# LCD_Disp_AIR.net
KiCad netlist of a schematic drawn in EAGLE
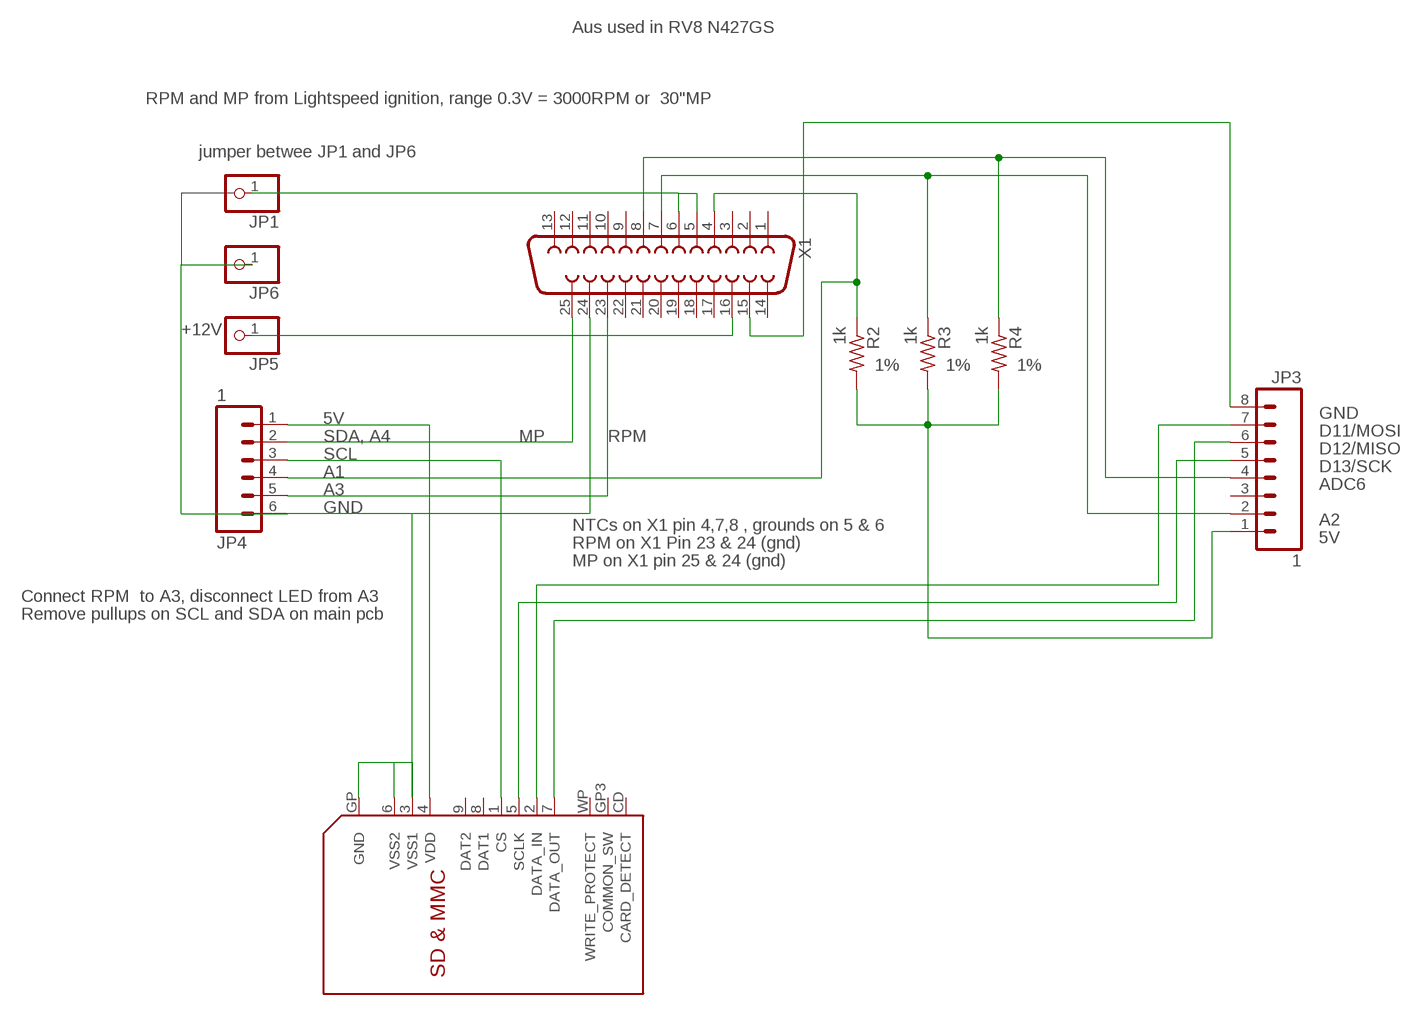
[diagram p0: schematic, sheet 1]

(export (version "E")
  (design (tool "Eeschema 10.0.6"))
  (components
    (comp (ref "JP1")
      (value "PINHD-1X1CB")
      (footprint "eagle-import:1X01-CLEANBIG")
      (libsource (lib "eagle-import") (part "PINHD-1X1CB"))
    )
    (comp (ref "JP3")
      (value "1")
      (footprint "eagle-import:1X08")
      (libsource (lib "eagle-import") (part "M081X08"))
    )
    (comp (ref "JP4")
      (value "1")
      (footprint "eagle-import:1X06")
      (libsource (lib "eagle-import") (part "M06SIP"))
    )
    (comp (ref "JP5")
      (value "PINHD-1X1")
      (footprint "eagle-import:1X01")
      (libsource (lib "eagle-import") (part "PINHD-1X1"))
    )
    (comp (ref "JP6")
      (value "PINHD-1X1CB")
      (footprint "eagle-import:1X01-CLEANBIG")
      (libsource (lib "eagle-import") (part "PINHD-1X1CB"))
    )
    (comp (ref "R2")
      (value "1k")
      (footprint "eagle-import:0204_7")
      (libsource (lib "eagle-import") (part "R-US_0204/7"))
    )
    (comp (ref "R3")
      (value "1k")
      (footprint "eagle-import:0204_7")
      (libsource (lib "eagle-import") (part "R-US_0204/7"))
    )
    (comp (ref "R4")
      (value "1k")
      (footprint "eagle-import:0204_7")
      (libsource (lib "eagle-import") (part "R-US_0204/7"))
    )
    (comp (ref "U$1")
      (value "SDMMC06132")
      (footprint "eagle-import:06132")
      (libsource (lib "eagle-import") (part "SDMMC06132"))
    )
    (comp (ref "X1")
      (value "DB25_FEMALEVB")
      (footprint "eagle-import:F25VB")
      (libsource (lib "eagle-import") (part "DB25_FEMALEVB"))
    )
  )
  (nets
    (net (code "1") (name "/+12V") (class "Default")
      (node (ref "JP5") (pin "1") (pinfunction "1_1") (pintype "passive"))
      (node (ref "X1") (pin "16") (pinfunction "16_16") (pintype "passive"))
    )
    (net (code "2") (name "Net-(JP1-Pad1)") (class "Default")
      (node (ref "JP1") (pin "1") (pinfunction "1_1") (pintype "passive"))
      (node (ref "X1") (pin "5") (pinfunction "5_5") (pintype "passive"))
      (node (ref "X1") (pin "6") (pinfunction "6_6") (pintype "passive"))
    )
    (net (code "3") (name "Net-(JP3-Pad1)") (class "Default")
      (node (ref "JP3") (pin "1") (pinfunction "1_1") (pintype "passive"))
      (node (ref "R2") (pin "2") (pinfunction "2_2") (pintype "passive"))
      (node (ref "R3") (pin "2") (pinfunction "2_2") (pintype "passive"))
      (node (ref "R4") (pin "2") (pinfunction "2_2") (pintype "passive"))
    )
    (net (code "4") (name "Net-(JP3-Pad2)") (class "Default")
      (node (ref "JP3") (pin "2") (pinfunction "2_2") (pintype "passive"))
      (node (ref "R3") (pin "1") (pinfunction "1_1") (pintype "passive"))
      (node (ref "X1") (pin "7") (pinfunction "7_7") (pintype "passive"))
    )
    (net (code "5") (name "Net-(JP3-Pad4)") (class "Default")
      (node (ref "JP3") (pin "4") (pinfunction "4_4") (pintype "passive"))
      (node (ref "R4") (pin "1") (pinfunction "1_1") (pintype "passive"))
      (node (ref "X1") (pin "8") (pinfunction "8_8") (pintype "passive"))
    )
    (net (code "6") (name "Net-(JP3-Pad8)") (class "Default")
      (node (ref "JP3") (pin "8") (pinfunction "8_8") (pintype "passive"))
      (node (ref "X1") (pin "15") (pinfunction "15_15") (pintype "passive"))
    )
    (net (code "7") (name "Net-(JP4-Pad2)") (class "Default")
      (node (ref "JP4") (pin "2") (pinfunction "2_2") (pintype "passive"))
      (node (ref "X1") (pin "25") (pinfunction "25_25") (pintype "passive"))
    )
    (net (code "8") (name "Net-(JP4-Pad4)") (class "Default")
      (node (ref "JP4") (pin "4") (pinfunction "4_4") (pintype "passive"))
      (node (ref "R2") (pin "1") (pinfunction "1_1") (pintype "passive"))
      (node (ref "X1") (pin "4") (pinfunction "4_4") (pintype "passive"))
    )
    (net (code "9") (name "Net-(JP4-Pad5)") (class "Default")
      (node (ref "JP4") (pin "5") (pinfunction "5_5") (pintype "passive"))
      (node (ref "X1") (pin "23") (pinfunction "23_23") (pintype "passive"))
    )
    (net (code "10") (name "Net-(U$1-CS)") (class "Default")
      (node (ref "JP4") (pin "3") (pinfunction "3_3") (pintype "passive"))
      (node (ref "U$1") (pin "1") (pinfunction "CS_1") (pintype "input"))
    )
    (net (code "11") (name "Net-(U$1-DATA_IN)") (class "Default")
      (node (ref "JP3") (pin "7") (pinfunction "7_7") (pintype "passive"))
      (node (ref "U$1") (pin "2") (pinfunction "DATA_IN_2") (pintype "input"))
    )
    (net (code "12") (name "Net-(U$1-DATA_OUT)") (class "Default")
      (node (ref "JP3") (pin "6") (pinfunction "6_6") (pintype "passive"))
      (node (ref "U$1") (pin "7") (pinfunction "DATA_OUT_7") (pintype "output"))
    )
    (net (code "13") (name "Net-(U$1-GND)") (class "Default")
      (node (ref "JP4") (pin "6") (pinfunction "6_6") (pintype "passive"))
      (node (ref "JP6") (pin "1") (pinfunction "1_1") (pintype "passive"))
      (node (ref "U$1") (pin "3") (pinfunction "VSS1_3") (pintype "power_in"))
      (node (ref "U$1") (pin "6") (pinfunction "VSS2_6") (pintype "power_in"))
      (node (ref "U$1") (pin "GP") (pinfunction "GND_GP") (pintype "power_in"))
      (node (ref "X1") (pin "24") (pinfunction "24_24") (pintype "passive"))
    )
    (net (code "14") (name "Net-(U$1-SCLK)") (class "Default")
      (node (ref "JP3") (pin "5") (pinfunction "5_5") (pintype "passive"))
      (node (ref "U$1") (pin "5") (pinfunction "SCLK_5") (pintype "input"))
    )
    (net (code "15") (name "Net-(U$1-VDD)") (class "Default")
      (node (ref "JP4") (pin "1") (pinfunction "1_1") (pintype "passive"))
      (node (ref "U$1") (pin "4") (pinfunction "VDD_4") (pintype "power_in"))
    )
    (net (code "16") (name "unconnected-(JP3-Pad3)") (class "Default")
      (node (ref "JP3") (pin "3") (pinfunction "3_3") (pintype "passive"))
    )
    (net (code "17") (name "unconnected-(U$1-CARD_DETECT-PadCD)") (class "Default")
      (node (ref "U$1") (pin "CD") (pinfunction "CARD_DETECT_CD") (pintype "passive"))
    )
    (net (code "18") (name "unconnected-(U$1-COMMON_SW-PadGP3)") (class "Default")
      (node (ref "U$1") (pin "GP3") (pinfunction "COMMON_SW_GP3") (pintype "passive"))
    )
    (net (code "19") (name "unconnected-(U$1-DAT1-Pad8)") (class "Default")
      (node (ref "U$1") (pin "8") (pinfunction "DAT1_8") (pintype "bidirectional"))
    )
    (net (code "20") (name "unconnected-(U$1-DAT2-Pad9)") (class "Default")
      (node (ref "U$1") (pin "9") (pinfunction "DAT2_9") (pintype "bidirectional"))
    )
    (net (code "21") (name "unconnected-(U$1-WRITE_PROTECT-PadWP)") (class "Default")
      (node (ref "U$1") (pin "WP") (pinfunction "WRITE_PROTECT_WP") (pintype "passive"))
    )
    (net (code "22") (name "unconnected-(X1-Pad1)") (class "Default")
      (node (ref "X1") (pin "1") (pinfunction "1_1") (pintype "passive"))
    )
    (net (code "23") (name "unconnected-(X1-Pad2)") (class "Default")
      (node (ref "X1") (pin "2") (pinfunction "2_2") (pintype "passive"))
    )
    (net (code "24") (name "unconnected-(X1-Pad3)") (class "Default")
      (node (ref "X1") (pin "3") (pinfunction "3_3") (pintype "passive"))
    )
    (net (code "25") (name "unconnected-(X1-Pad9)") (class "Default")
      (node (ref "X1") (pin "9") (pinfunction "9_9") (pintype "passive"))
    )
    (net (code "26") (name "unconnected-(X1-Pad10)") (class "Default")
      (node (ref "X1") (pin "10") (pinfunction "10_10") (pintype "passive"))
    )
    (net (code "27") (name "unconnected-(X1-Pad11)") (class "Default")
      (node (ref "X1") (pin "11") (pinfunction "11_11") (pintype "passive"))
    )
    (net (code "28") (name "unconnected-(X1-Pad12)") (class "Default")
      (node (ref "X1") (pin "12") (pinfunction "12_12") (pintype "passive"))
    )
    (net (code "29") (name "unconnected-(X1-Pad13)") (class "Default")
      (node (ref "X1") (pin "13") (pinfunction "13_13") (pintype "passive"))
    )
    (net (code "30") (name "unconnected-(X1-Pad14)") (class "Default")
      (node (ref "X1") (pin "14") (pinfunction "14_14") (pintype "passive"))
    )
    (net (code "31") (name "unconnected-(X1-Pad17)") (class "Default")
      (node (ref "X1") (pin "17") (pinfunction "17_17") (pintype "passive"))
    )
    (net (code "32") (name "unconnected-(X1-Pad18)") (class "Default")
      (node (ref "X1") (pin "18") (pinfunction "18_18") (pintype "passive"))
    )
    (net (code "33") (name "unconnected-(X1-Pad19)") (class "Default")
      (node (ref "X1") (pin "19") (pinfunction "19_19") (pintype "passive"))
    )
    (net (code "34") (name "unconnected-(X1-Pad20)") (class "Default")
      (node (ref "X1") (pin "20") (pinfunction "20_20") (pintype "passive"))
    )
    (net (code "35") (name "unconnected-(X1-Pad21)") (class "Default")
      (node (ref "X1") (pin "21") (pinfunction "21_21") (pintype "passive"))
    )
    (net (code "36") (name "unconnected-(X1-Pad22)") (class "Default")
      (node (ref "X1") (pin "22") (pinfunction "22_22") (pintype "passive"))
    )
  )
)
